# AQ_sensor_SIGFOX.net
KiCad netlist of a schematic drawn in EAGLE
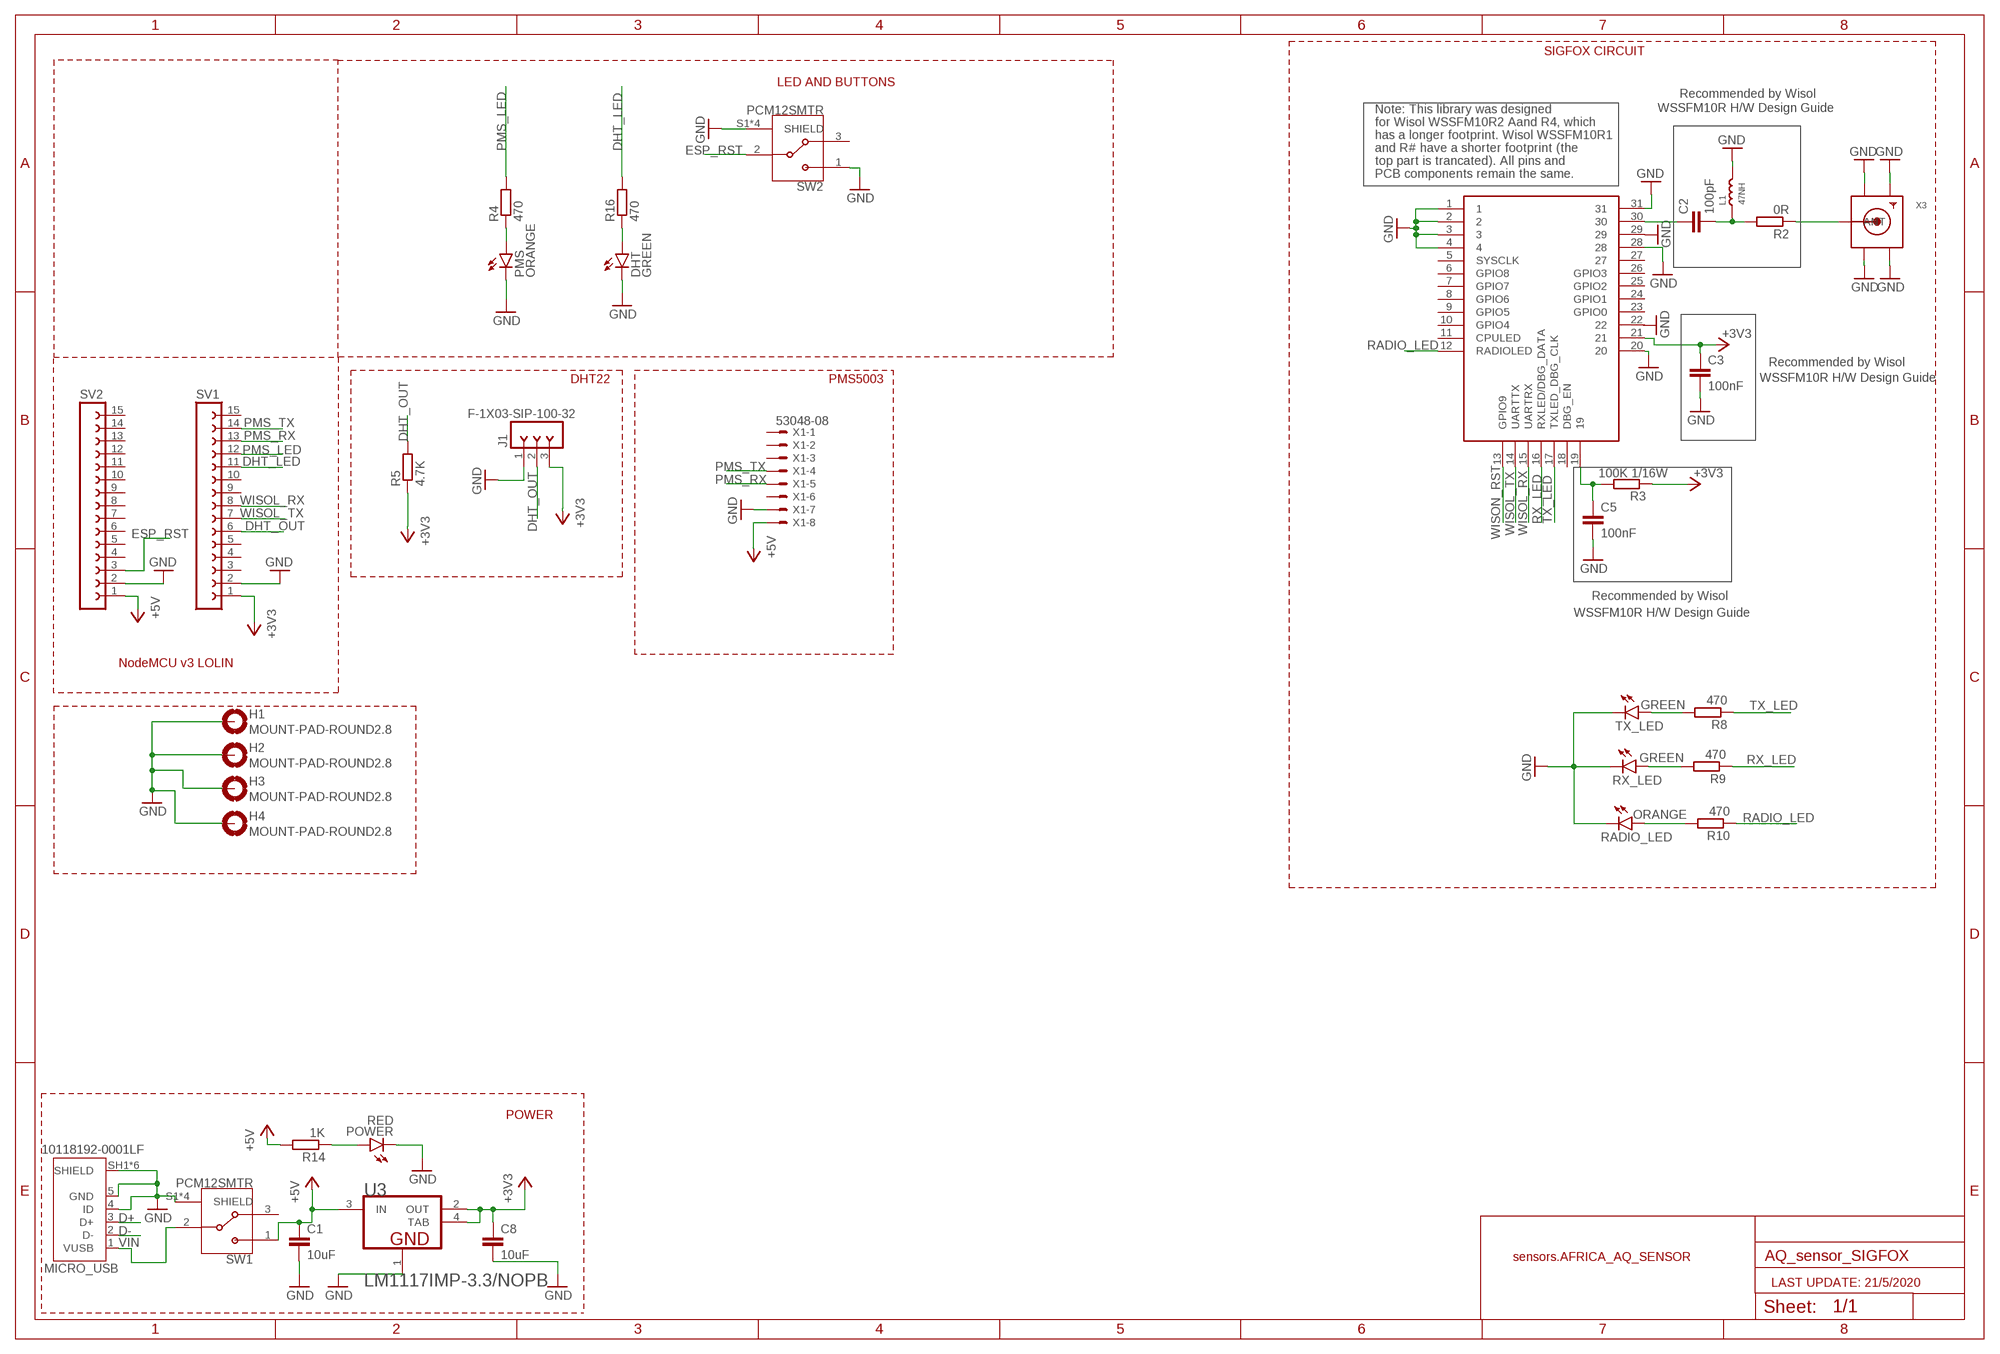
[diagram p0: schematic, sheet 1]

(export (version "E")
  (design (tool "Eeschema 10.0.6"))
  (components
    (comp (ref "C1")
      (value "10uF")
      (footprint "eagle-import:C0603")
      (libsource (lib "eagle-import") (part "C-EUC0603"))
    )
    (comp (ref "C2")
      (value "100pF")
      (footprint "eagle-import:C0603")
      (libsource (lib "eagle-import") (part "C-EUC0603"))
    )
    (comp (ref "C3")
      (value "100nF")
      (footprint "eagle-import:C0603")
      (libsource (lib "eagle-import") (part "C-EUC0603"))
    )
    (comp (ref "C5")
      (value "100nF")
      (footprint "eagle-import:C0603")
      (libsource (lib "eagle-import") (part "C-EUC0603"))
    )
    (comp (ref "C8")
      (value "10uF")
      (footprint "eagle-import:C0603")
      (libsource (lib "eagle-import") (part "C-EUC0603"))
    )
    (comp (ref "DHT")
      (value "GREEN")
      (footprint "eagle-import:CHIP-LED0603")
      (libsource (lib "eagle-import") (part "LEDCHIP-LED0603"))
    )
    (comp (ref "H1")
      (value "MOUNT-PAD-ROUND2.8")
      (footprint "eagle-import:2,8-PAD")
      (libsource (lib "eagle-import") (part "MOUNT-PAD-ROUND2.8"))
    )
    (comp (ref "H2")
      (value "MOUNT-PAD-ROUND2.8")
      (footprint "eagle-import:2,8-PAD")
      (libsource (lib "eagle-import") (part "MOUNT-PAD-ROUND2.8"))
    )
    (comp (ref "H3")
      (value "MOUNT-PAD-ROUND2.8")
      (footprint "eagle-import:2,8-PAD")
      (libsource (lib "eagle-import") (part "MOUNT-PAD-ROUND2.8"))
    )
    (comp (ref "H4")
      (value "MOUNT-PAD-ROUND2.8")
      (footprint "eagle-import:2,8-PAD")
      (libsource (lib "eagle-import") (part "MOUNT-PAD-ROUND2.8"))
    )
    (comp (ref "J1")
      (value "F-1X03-SIP-100-32")
      (footprint "eagle-import:SIP-100-03-32")
      (libsource (lib "eagle-import") (part "F-1X03-SIP-100-32"))
    )
    (comp (ref "L1")
      (value "47NH")
      (footprint "eagle-import:L0805")
      (fields (field (name "MPN") "LQM2MPN2R2MG0"))
      (libsource (lib "eagle-import") (part "SMD-INDUCTOR-2.2UH-20%-1.2A(0805)"))
    )
    (comp (ref "MICRO_USB")
      (value "10118192-0001LF")
      (footprint "eagle-import:AMPHENOL_10118192-0001LF")
      (fields (field (name "MF") "Amphenol ICC"))
      (libsource (lib "eagle-import") (part "10118192-0001LF"))
    )
    (comp (ref "PMS")
      (value "ORANGE")
      (footprint "eagle-import:CHIP-LED0603")
      (libsource (lib "eagle-import") (part "LEDCHIP-LED0603"))
    )
    (comp (ref "POWER")
      (value "RED")
      (footprint "eagle-import:CHIP-LED0603")
      (libsource (lib "eagle-import") (part "LEDCHIP-LED0603"))
    )
    (comp (ref "R2")
      (value "0R")
      (footprint "eagle-import:R0603")
      (libsource (lib "eagle-import") (part "R-EU_R0603"))
    )
    (comp (ref "R3")
      (value "100K 1/16W")
      (footprint "eagle-import:R0603")
      (libsource (lib "eagle-import") (part "R-EU_R0603"))
    )
    (comp (ref "R4")
      (value "470")
      (footprint "eagle-import:R0603")
      (libsource (lib "eagle-import") (part "R-EU_R0603"))
    )
    (comp (ref "R5")
      (value "4.7K")
      (footprint "eagle-import:R0603")
      (libsource (lib "eagle-import") (part "R-EU_R0603"))
    )
    (comp (ref "R8")
      (value "470")
      (footprint "eagle-import:R0603")
      (libsource (lib "eagle-import") (part "R-EU_R0603"))
    )
    (comp (ref "R9")
      (value "470")
      (footprint "eagle-import:R0603")
      (libsource (lib "eagle-import") (part "R-EU_R0603"))
    )
    (comp (ref "R10")
      (value "470")
      (footprint "eagle-import:R0603")
      (libsource (lib "eagle-import") (part "R-EU_R0603"))
    )
    (comp (ref "R14")
      (value "1K")
      (footprint "eagle-import:R0603")
      (libsource (lib "eagle-import") (part "R-EU_R0603"))
    )
    (comp (ref "R16")
      (value "470")
      (footprint "eagle-import:R0603")
      (libsource (lib "eagle-import") (part "R-EU_R0603"))
    )
    (comp (ref "RADIO_LED")
      (value "ORANGE")
      (footprint "eagle-import:CHIP-LED0603")
      (libsource (lib "eagle-import") (part "LEDCHIP-LED0603"))
    )
    (comp (ref "RX_LED")
      (value "GREEN")
      (footprint "eagle-import:CHIP-LED0603")
      (libsource (lib "eagle-import") (part "LEDCHIP-LED0603"))
    )
    (comp (ref "SV1")
      (value "FE15-1")
      (footprint "eagle-import:FE15")
      (libsource (lib "eagle-import") (part "FE15-1"))
    )
    (comp (ref "SV2")
      (value "FE15-1")
      (footprint "eagle-import:FE15")
      (libsource (lib "eagle-import") (part "FE15-1"))
    )
    (comp (ref "SW1")
      (value "PCM12SMTR")
      (footprint "eagle-import:SW_PCM12SMTR")
      (fields (field (name "MF") "C&K"))
      (libsource (lib "eagle-import") (part "PCM12SMTR"))
    )
    (comp (ref "SW2")
      (value "PCM12SMTR")
      (footprint "eagle-import:SW_PCM12SMTR")
      (fields (field (name "MF") "C&K"))
      (libsource (lib "eagle-import") (part "PCM12SMTR"))
    )
    (comp (ref "TX_LED")
      (value "GREEN")
      (footprint "eagle-import:CHIP-LED0603")
      (libsource (lib "eagle-import") (part "LEDCHIP-LED0603"))
    )
    (comp (ref "U$1")
      (value "WSSFM10RWSSFM10R2R4")
      (footprint "eagle-import:WSSFM10R")
      (libsource (lib "eagle-import") (part "WSSFM10RWSSFM10R2R4"))
    )
    (comp (ref "U3")
      (value "TEXAS_INSTRUMENTS_LM1117IMP-3.3-NOPBTEXAS_INSTRUMENTS_LM1117IMP-3.3-NOPB_0_0")
      (footprint "eagle-import:TEXAS_INSTRUMENTS_LM1117IMP-3.3-NOPB_0")
      (fields (field (name "MF") "Texas Instruments") (field (name "MPN") "LM1117IMP-3.3/NOPB"))
      (libsource (lib "eagle-import") (part "TEXAS_INSTRUMENTS_LM1117IMP-3.3-NOPBTEXAS_INSTRUMENTS_LM1117IMP-3.3-NOPB_0_0"))
    )
    (comp (ref "X1")
      (value "53048-08")
      (footprint "eagle-import:53048-08")
      (fields (field (name "MF") "WALDOM/MOLEX") (field (name "MPN") "53048-0810"))
      (libsource (lib "eagle-import") (part "53?-08048"))
    )
    (comp (ref "X3")
      (value "SMACONNECTOR_EDGE_UFL")
      (footprint "eagle-import:SMA_EDGELAUNCH_UFL")
      (libsource (lib "eagle-import") (part "SMACONNECTOR_EDGE_UFL"))
    )
  )
  (nets
    (net (code "1") (name "+3V3") (class "Default")
      (node (ref "C3") (pin "1") (pinfunction "1_1") (pintype "passive"))
      (node (ref "C8") (pin "1") (pinfunction "1_1") (pintype "passive"))
      (node (ref "J1") (pin "3") (pinfunction "3_3") (pintype "passive"))
      (node (ref "R3") (pin "1") (pinfunction "1_1") (pintype "passive"))
      (node (ref "R5") (pin "1") (pinfunction "1_1") (pintype "passive"))
      (node (ref "SV1") (pin "1") (pinfunction "1_1") (pintype "passive"))
      (node (ref "U$1") (pin "21") (pinfunction "21_21") (pintype "bidirectional"))
      (node (ref "U3") (pin "2") (pinfunction "OUT_2") (pintype "power_in"))
      (node (ref "U3") (pin "4") (pinfunction "TAB_4") (pintype "power_in"))
    )
    (net (code "2") (name "+5V") (class "Default")
      (node (ref "C1") (pin "1") (pinfunction "1_1") (pintype "passive"))
      (node (ref "R14") (pin "2") (pinfunction "2_2") (pintype "passive"))
      (node (ref "SV2") (pin "1") (pinfunction "1_1") (pintype "passive"))
      (node (ref "SW1") (pin "1") (pinfunction "1_1") (pintype "passive"))
      (node (ref "U3") (pin "3") (pinfunction "IN_3") (pintype "power_in"))
      (node (ref "X1") (pin "8") (pinfunction "S_8") (pintype "passive"))
    )
    (net (code "3") (name "/D+") (class "Default")
      (node (ref "MICRO_USB") (pin "3") (pinfunction "D+_3") (pintype "passive"))
    )
    (net (code "4") (name "/D-") (class "Default")
      (node (ref "MICRO_USB") (pin "2") (pinfunction "D-_2") (pintype "passive"))
    )
    (net (code "5") (name "/DHT_LED") (class "Default")
      (node (ref "R16") (pin "2") (pinfunction "2_2") (pintype "passive"))
      (node (ref "SV1") (pin "11") (pinfunction "11_11") (pintype "passive"))
    )
    (net (code "6") (name "/DHT_OUT") (class "Default")
      (node (ref "J1") (pin "2") (pinfunction "2_2") (pintype "passive"))
      (node (ref "R5") (pin "2") (pinfunction "2_2") (pintype "passive"))
      (node (ref "SV1") (pin "6") (pinfunction "6_6") (pintype "passive"))
    )
    (net (code "7") (name "/ESP_RST") (class "Default")
      (node (ref "SV2") (pin "3") (pinfunction "3_3") (pintype "passive"))
      (node (ref "SW2") (pin "2") (pinfunction "2_2") (pintype "passive"))
    )
    (net (code "8") (name "/PMS_LED") (class "Default")
      (node (ref "R4") (pin "2") (pinfunction "2_2") (pintype "passive"))
      (node (ref "SV1") (pin "12") (pinfunction "12_12") (pintype "passive"))
    )
    (net (code "9") (name "/PMS_RX") (class "Default")
      (node (ref "SV1") (pin "13") (pinfunction "13_13") (pintype "passive"))
      (node (ref "X1") (pin "5") (pinfunction "S_5") (pintype "passive"))
    )
    (net (code "10") (name "/PMS_TX") (class "Default")
      (node (ref "SV1") (pin "14") (pinfunction "14_14") (pintype "passive"))
      (node (ref "X1") (pin "4") (pinfunction "S_4") (pintype "passive"))
    )
    (net (code "11") (name "/RADIO_LED") (class "Default")
      (node (ref "R10") (pin "1") (pinfunction "1_1") (pintype "passive"))
      (node (ref "U$1") (pin "12") (pinfunction "RADIOLED_12") (pintype "bidirectional"))
    )
    (net (code "12") (name "/RX_LED") (class "Default")
      (node (ref "R9") (pin "1") (pinfunction "1_1") (pintype "passive"))
      (node (ref "U$1") (pin "16") (pinfunction "RXLED/DBG_DATA_16") (pintype "bidirectional"))
    )
    (net (code "13") (name "/TX_LED") (class "Default")
      (node (ref "R8") (pin "1") (pinfunction "1_1") (pintype "passive"))
      (node (ref "U$1") (pin "17") (pinfunction "TXLED_DBG_CLK_17") (pintype "bidirectional"))
    )
    (net (code "14") (name "/VIN") (class "Default")
      (node (ref "MICRO_USB") (pin "1") (pinfunction "VUSB_1") (pintype "passive"))
      (node (ref "SW1") (pin "2") (pinfunction "2_2") (pintype "passive"))
    )
    (net (code "15") (name "/WISOL_RX") (class "Default")
      (node (ref "SV1") (pin "8") (pinfunction "8_8") (pintype "passive"))
      (node (ref "U$1") (pin "15") (pinfunction "UARTRX_15") (pintype "bidirectional"))
    )
    (net (code "16") (name "/WISOL_TX") (class "Default")
      (node (ref "SV1") (pin "7") (pinfunction "7_7") (pintype "passive"))
      (node (ref "U$1") (pin "14") (pinfunction "UARTTX_14") (pintype "bidirectional"))
    )
    (net (code "17") (name "/WISON_RST") (class "Default")
      (node (ref "U$1") (pin "13") (pinfunction "GPIO9_13") (pintype "bidirectional"))
    )
    (net (code "18") (name "GND") (class "Default")
      (node (ref "C1") (pin "2") (pinfunction "2_2") (pintype "passive"))
      (node (ref "C3") (pin "2") (pinfunction "2_2") (pintype "passive"))
      (node (ref "C5") (pin "2") (pinfunction "2_2") (pintype "passive"))
      (node (ref "C8") (pin "2") (pinfunction "2_2") (pintype "passive"))
      (node (ref "DHT") (pin "C") (pinfunction "C_C") (pintype "passive"))
      (node (ref "H1") (pin "B2,8") (pinfunction "MOUNT_B2,8") (pintype "passive"))
      (node (ref "H2") (pin "B2,8") (pinfunction "MOUNT_B2,8") (pintype "passive"))
      (node (ref "H3") (pin "B2,8") (pinfunction "MOUNT_B2,8") (pintype "passive"))
      (node (ref "H4") (pin "B2,8") (pinfunction "MOUNT_B2,8") (pintype "passive"))
      (node (ref "J1") (pin "1") (pinfunction "1_1") (pintype "passive"))
      (node (ref "L1") (pin "2") (pinfunction "2_2") (pintype "passive"))
      (node (ref "MICRO_USB") (pin "4") (pinfunction "ID_4") (pintype "passive"))
      (node (ref "MICRO_USB") (pin "5") (pinfunction "GND_5") (pintype "passive"))
      (node (ref "MICRO_USB") (pin "SH1") (pinfunction "SHIELD_SH1") (pintype "passive"))
      (node (ref "MICRO_USB") (pin "SH2") (pinfunction "SHIELD_SH2") (pintype "passive"))
      (node (ref "MICRO_USB") (pin "SH3") (pinfunction "SHIELD_SH3") (pintype "passive"))
      (node (ref "MICRO_USB") (pin "SH4") (pinfunction "SHIELD_SH4") (pintype "passive"))
      (node (ref "MICRO_USB") (pin "SH5") (pinfunction "SHIELD_SH5") (pintype "passive"))
      (node (ref "MICRO_USB") (pin "SH6") (pinfunction "SHIELD_SH6") (pintype "passive"))
      (node (ref "PMS") (pin "C") (pinfunction "C_C") (pintype "passive"))
      (node (ref "POWER") (pin "C") (pinfunction "C_C") (pintype "passive"))
      (node (ref "RADIO_LED") (pin "C") (pinfunction "C_C") (pintype "passive"))
      (node (ref "RX_LED") (pin "C") (pinfunction "C_C") (pintype "passive"))
      (node (ref "SV1") (pin "2") (pinfunction "2_2") (pintype "passive"))
      (node (ref "SV2") (pin "2") (pinfunction "2_2") (pintype "passive"))
      (node (ref "SW1") (pin "S1") (pinfunction "SHIELD_S1") (pintype "passive"))
      (node (ref "SW1") (pin "S2") (pinfunction "SHIELD_S2") (pintype "passive"))
      (node (ref "SW1") (pin "S3") (pinfunction "SHIELD_S3") (pintype "passive"))
      (node (ref "SW1") (pin "S4") (pinfunction "SHIELD_S4") (pintype "passive"))
      (node (ref "SW2") (pin "1") (pinfunction "1_1") (pintype "passive"))
      (node (ref "SW2") (pin "S1") (pinfunction "SHIELD_S1") (pintype "passive"))
      (node (ref "SW2") (pin "S2") (pinfunction "SHIELD_S2") (pintype "passive"))
      (node (ref "SW2") (pin "S3") (pinfunction "SHIELD_S3") (pintype "passive"))
      (node (ref "SW2") (pin "S4") (pinfunction "SHIELD_S4") (pintype "passive"))
      (node (ref "TX_LED") (pin "C") (pinfunction "C_C") (pintype "passive"))
      (node (ref "U$1") (pin "1") (pinfunction "1_1") (pintype "bidirectional"))
      (node (ref "U$1") (pin "2") (pinfunction "2_2") (pintype "bidirectional"))
      (node (ref "U$1") (pin "20") (pinfunction "20_20") (pintype "bidirectional"))
      (node (ref "U$1") (pin "28") (pinfunction "28_28") (pintype "bidirectional"))
      (node (ref "U$1") (pin "29") (pinfunction "29_29") (pintype "bidirectional"))
      (node (ref "U$1") (pin "3") (pinfunction "3_3") (pintype "bidirectional"))
      (node (ref "U$1") (pin "31") (pinfunction "31_31") (pintype "bidirectional"))
      (node (ref "U$1") (pin "4") (pinfunction "4_4") (pintype "bidirectional"))
      (node (ref "U3") (pin "1") (pinfunction "GND_1") (pintype "power_in"))
      (node (ref "X1") (pin "7") (pinfunction "S_7") (pintype "passive"))
      (node (ref "X3") (pin "GND@1") (pinfunction "GND1_GND@1") (pintype "power_in"))
      (node (ref "X3") (pin "GND@2") (pinfunction "GND2_GND@2") (pintype "power_in"))
      (node (ref "X3") (pin "GND@3") (pinfunction "GND3_GND@3") (pintype "power_in"))
      (node (ref "X3") (pin "GND@4") (pinfunction "GND4_GND@4") (pintype "power_in"))
    )
    (net (code "19") (name "Net-(C2-Pad1)") (class "Default")
      (node (ref "C2") (pin "1") (pinfunction "1_1") (pintype "passive"))
      (node (ref "U$1") (pin "30") (pinfunction "30_30") (pintype "bidirectional"))
    )
    (net (code "20") (name "Net-(C2-Pad2)") (class "Default")
      (node (ref "C2") (pin "2") (pinfunction "2_2") (pintype "passive"))
      (node (ref "L1") (pin "1") (pinfunction "1_1") (pintype "passive"))
      (node (ref "R2") (pin "2") (pinfunction "2_2") (pintype "passive"))
    )
    (net (code "21") (name "Net-(C5-Pad1)") (class "Default")
      (node (ref "C5") (pin "1") (pinfunction "1_1") (pintype "passive"))
      (node (ref "R3") (pin "2") (pinfunction "2_2") (pintype "passive"))
      (node (ref "U$1") (pin "19") (pinfunction "19_19") (pintype "bidirectional"))
    )
    (net (code "22") (name "Net-(DHT-PadA)") (class "Default")
      (node (ref "DHT") (pin "A") (pinfunction "A_A") (pintype "passive"))
      (node (ref "R16") (pin "1") (pinfunction "1_1") (pintype "passive"))
    )
    (net (code "23") (name "Net-(PMS-PadA)") (class "Default")
      (node (ref "PMS") (pin "A") (pinfunction "A_A") (pintype "passive"))
      (node (ref "R4") (pin "1") (pinfunction "1_1") (pintype "passive"))
    )
    (net (code "24") (name "Net-(POWER-PadA)") (class "Default")
      (node (ref "POWER") (pin "A") (pinfunction "A_A") (pintype "passive"))
      (node (ref "R14") (pin "1") (pinfunction "1_1") (pintype "passive"))
    )
    (net (code "25") (name "Net-(R8-Pad2)") (class "Default")
      (node (ref "R8") (pin "2") (pinfunction "2_2") (pintype "passive"))
      (node (ref "TX_LED") (pin "A") (pinfunction "A_A") (pintype "passive"))
    )
    (net (code "26") (name "Net-(R9-Pad2)") (class "Default")
      (node (ref "R9") (pin "2") (pinfunction "2_2") (pintype "passive"))
      (node (ref "RX_LED") (pin "A") (pinfunction "A_A") (pintype "passive"))
    )
    (net (code "27") (name "Net-(R10-Pad2)") (class "Default")
      (node (ref "R10") (pin "2") (pinfunction "2_2") (pintype "passive"))
      (node (ref "RADIO_LED") (pin "A") (pinfunction "A_A") (pintype "passive"))
    )
    (net (code "28") (name "Net-(X3-ANT)") (class "Default")
      (node (ref "R2") (pin "1") (pinfunction "1_1") (pintype "passive"))
      (node (ref "X3") (pin "P") (pinfunction "ANT_P") (pintype "bidirectional"))
    )
    (net (code "29") (name "unconnected-(SV1-Pad3)") (class "Default")
      (node (ref "SV1") (pin "3") (pinfunction "3_3") (pintype "passive"))
    )
    (net (code "30") (name "unconnected-(SV1-Pad4)") (class "Default")
      (node (ref "SV1") (pin "4") (pinfunction "4_4") (pintype "passive"))
    )
    (net (code "31") (name "unconnected-(SV1-Pad5)") (class "Default")
      (node (ref "SV1") (pin "5") (pinfunction "5_5") (pintype "passive"))
    )
    (net (code "32") (name "unconnected-(SV1-Pad9)") (class "Default")
      (node (ref "SV1") (pin "9") (pinfunction "9_9") (pintype "passive"))
    )
    (net (code "33") (name "unconnected-(SV1-Pad10)") (class "Default")
      (node (ref "SV1") (pin "10") (pinfunction "10_10") (pintype "passive"))
    )
    (net (code "34") (name "unconnected-(SV1-Pad15)") (class "Default")
      (node (ref "SV1") (pin "15") (pinfunction "15_15") (pintype "passive"))
    )
    (net (code "35") (name "unconnected-(SV2-Pad4)") (class "Default")
      (node (ref "SV2") (pin "4") (pinfunction "4_4") (pintype "passive"))
    )
    (net (code "36") (name "unconnected-(SV2-Pad5)") (class "Default")
      (node (ref "SV2") (pin "5") (pinfunction "5_5") (pintype "passive"))
    )
    (net (code "37") (name "unconnected-(SV2-Pad6)") (class "Default")
      (node (ref "SV2") (pin "6") (pinfunction "6_6") (pintype "passive"))
    )
    (net (code "38") (name "unconnected-(SV2-Pad7)") (class "Default")
      (node (ref "SV2") (pin "7") (pinfunction "7_7") (pintype "passive"))
    )
    (net (code "39") (name "unconnected-(SV2-Pad8)") (class "Default")
      (node (ref "SV2") (pin "8") (pinfunction "8_8") (pintype "passive"))
    )
    (net (code "40") (name "unconnected-(SV2-Pad9)") (class "Default")
      (node (ref "SV2") (pin "9") (pinfunction "9_9") (pintype "passive"))
    )
    (net (code "41") (name "unconnected-(SV2-Pad10)") (class "Default")
      (node (ref "SV2") (pin "10") (pinfunction "10_10") (pintype "passive"))
    )
    (net (code "42") (name "unconnected-(SV2-Pad11)") (class "Default")
      (node (ref "SV2") (pin "11") (pinfunction "11_11") (pintype "passive"))
    )
    (net (code "43") (name "unconnected-(SV2-Pad12)") (class "Default")
      (node (ref "SV2") (pin "12") (pinfunction "12_12") (pintype "passive"))
    )
    (net (code "44") (name "unconnected-(SV2-Pad13)") (class "Default")
      (node (ref "SV2") (pin "13") (pinfunction "13_13") (pintype "passive"))
    )
    (net (code "45") (name "unconnected-(SV2-Pad14)") (class "Default")
      (node (ref "SV2") (pin "14") (pinfunction "14_14") (pintype "passive"))
    )
    (net (code "46") (name "unconnected-(SV2-Pad15)") (class "Default")
      (node (ref "SV2") (pin "15") (pinfunction "15_15") (pintype "passive"))
    )
    (net (code "47") (name "unconnected-(SW1-Pad3)") (class "Default")
      (node (ref "SW1") (pin "3") (pinfunction "3_3") (pintype "passive"))
    )
    (net (code "48") (name "unconnected-(SW2-Pad3)") (class "Default")
      (node (ref "SW2") (pin "3") (pinfunction "3_3") (pintype "passive"))
    )
    (net (code "49") (name "unconnected-(U$1-CPULED-Pad11)") (class "Default")
      (node (ref "U$1") (pin "11") (pinfunction "CPULED_11") (pintype "bidirectional"))
    )
    (net (code "50") (name "unconnected-(U$1-DBG_EN-Pad18)") (class "Default")
      (node (ref "U$1") (pin "18") (pinfunction "DBG_EN_18") (pintype "bidirectional"))
    )
    (net (code "51") (name "unconnected-(U$1-GPIO0-Pad23)") (class "Default")
      (node (ref "U$1") (pin "23") (pinfunction "GPIO0_23") (pintype "bidirectional"))
    )
    (net (code "52") (name "unconnected-(U$1-GPIO1-Pad24)") (class "Default")
      (node (ref "U$1") (pin "24") (pinfunction "GPIO1_24") (pintype "bidirectional"))
    )
    (net (code "53") (name "unconnected-(U$1-GPIO2-Pad25)") (class "Default")
      (node (ref "U$1") (pin "25") (pinfunction "GPIO2_25") (pintype "bidirectional"))
    )
    (net (code "54") (name "unconnected-(U$1-GPIO3-Pad26)") (class "Default")
      (node (ref "U$1") (pin "26") (pinfunction "GPIO3_26") (pintype "bidirectional"))
    )
    (net (code "55") (name "unconnected-(U$1-GPIO4-Pad10)") (class "Default")
      (node (ref "U$1") (pin "10") (pinfunction "GPIO4_10") (pintype "bidirectional"))
    )
    (net (code "56") (name "unconnected-(U$1-GPIO5-Pad9)") (class "Default")
      (node (ref "U$1") (pin "9") (pinfunction "GPIO5_9") (pintype "bidirectional"))
    )
    (net (code "57") (name "unconnected-(U$1-GPIO6-Pad8)") (class "Default")
      (node (ref "U$1") (pin "8") (pinfunction "GPIO6_8") (pintype "bidirectional"))
    )
    (net (code "58") (name "unconnected-(U$1-GPIO7-Pad7)") (class "Default")
      (node (ref "U$1") (pin "7") (pinfunction "GPIO7_7") (pintype "bidirectional"))
    )
    (net (code "59") (name "unconnected-(U$1-GPIO8-Pad6)") (class "Default")
      (node (ref "U$1") (pin "6") (pinfunction "GPIO8_6") (pintype "bidirectional"))
    )
    (net (code "60") (name "unconnected-(U$1-Pad22)") (class "Default")
      (node (ref "U$1") (pin "22") (pinfunction "22_22") (pintype "bidirectional"))
    )
    (net (code "61") (name "unconnected-(U$1-Pad27)") (class "Default")
      (node (ref "U$1") (pin "27") (pinfunction "27_27") (pintype "bidirectional"))
    )
    (net (code "62") (name "unconnected-(U$1-SYSCLK-Pad5)") (class "Default")
      (node (ref "U$1") (pin "5") (pinfunction "SYSCLK_5") (pintype "bidirectional"))
    )
    (net (code "63") (name "unconnected-(X1A-S-Pad1)") (class "Default")
      (node (ref "X1") (pin "1") (pinfunction "S_1") (pintype "passive"))
    )
    (net (code "64") (name "unconnected-(X1B-S-Pad2)") (class "Default")
      (node (ref "X1") (pin "2") (pinfunction "S_2") (pintype "passive"))
    )
    (net (code "65") (name "unconnected-(X1C-S-Pad3)") (class "Default")
      (node (ref "X1") (pin "3") (pinfunction "S_3") (pintype "passive"))
    )
    (net (code "66") (name "unconnected-(X1F-S-Pad6)") (class "Default")
      (node (ref "X1") (pin "6") (pinfunction "S_6") (pintype "passive"))
    )
  )
)
